# SAML21_Xplained_Pro_triple_input_power_s.net
KiCad netlist of a schematic drawn in Altium Designer
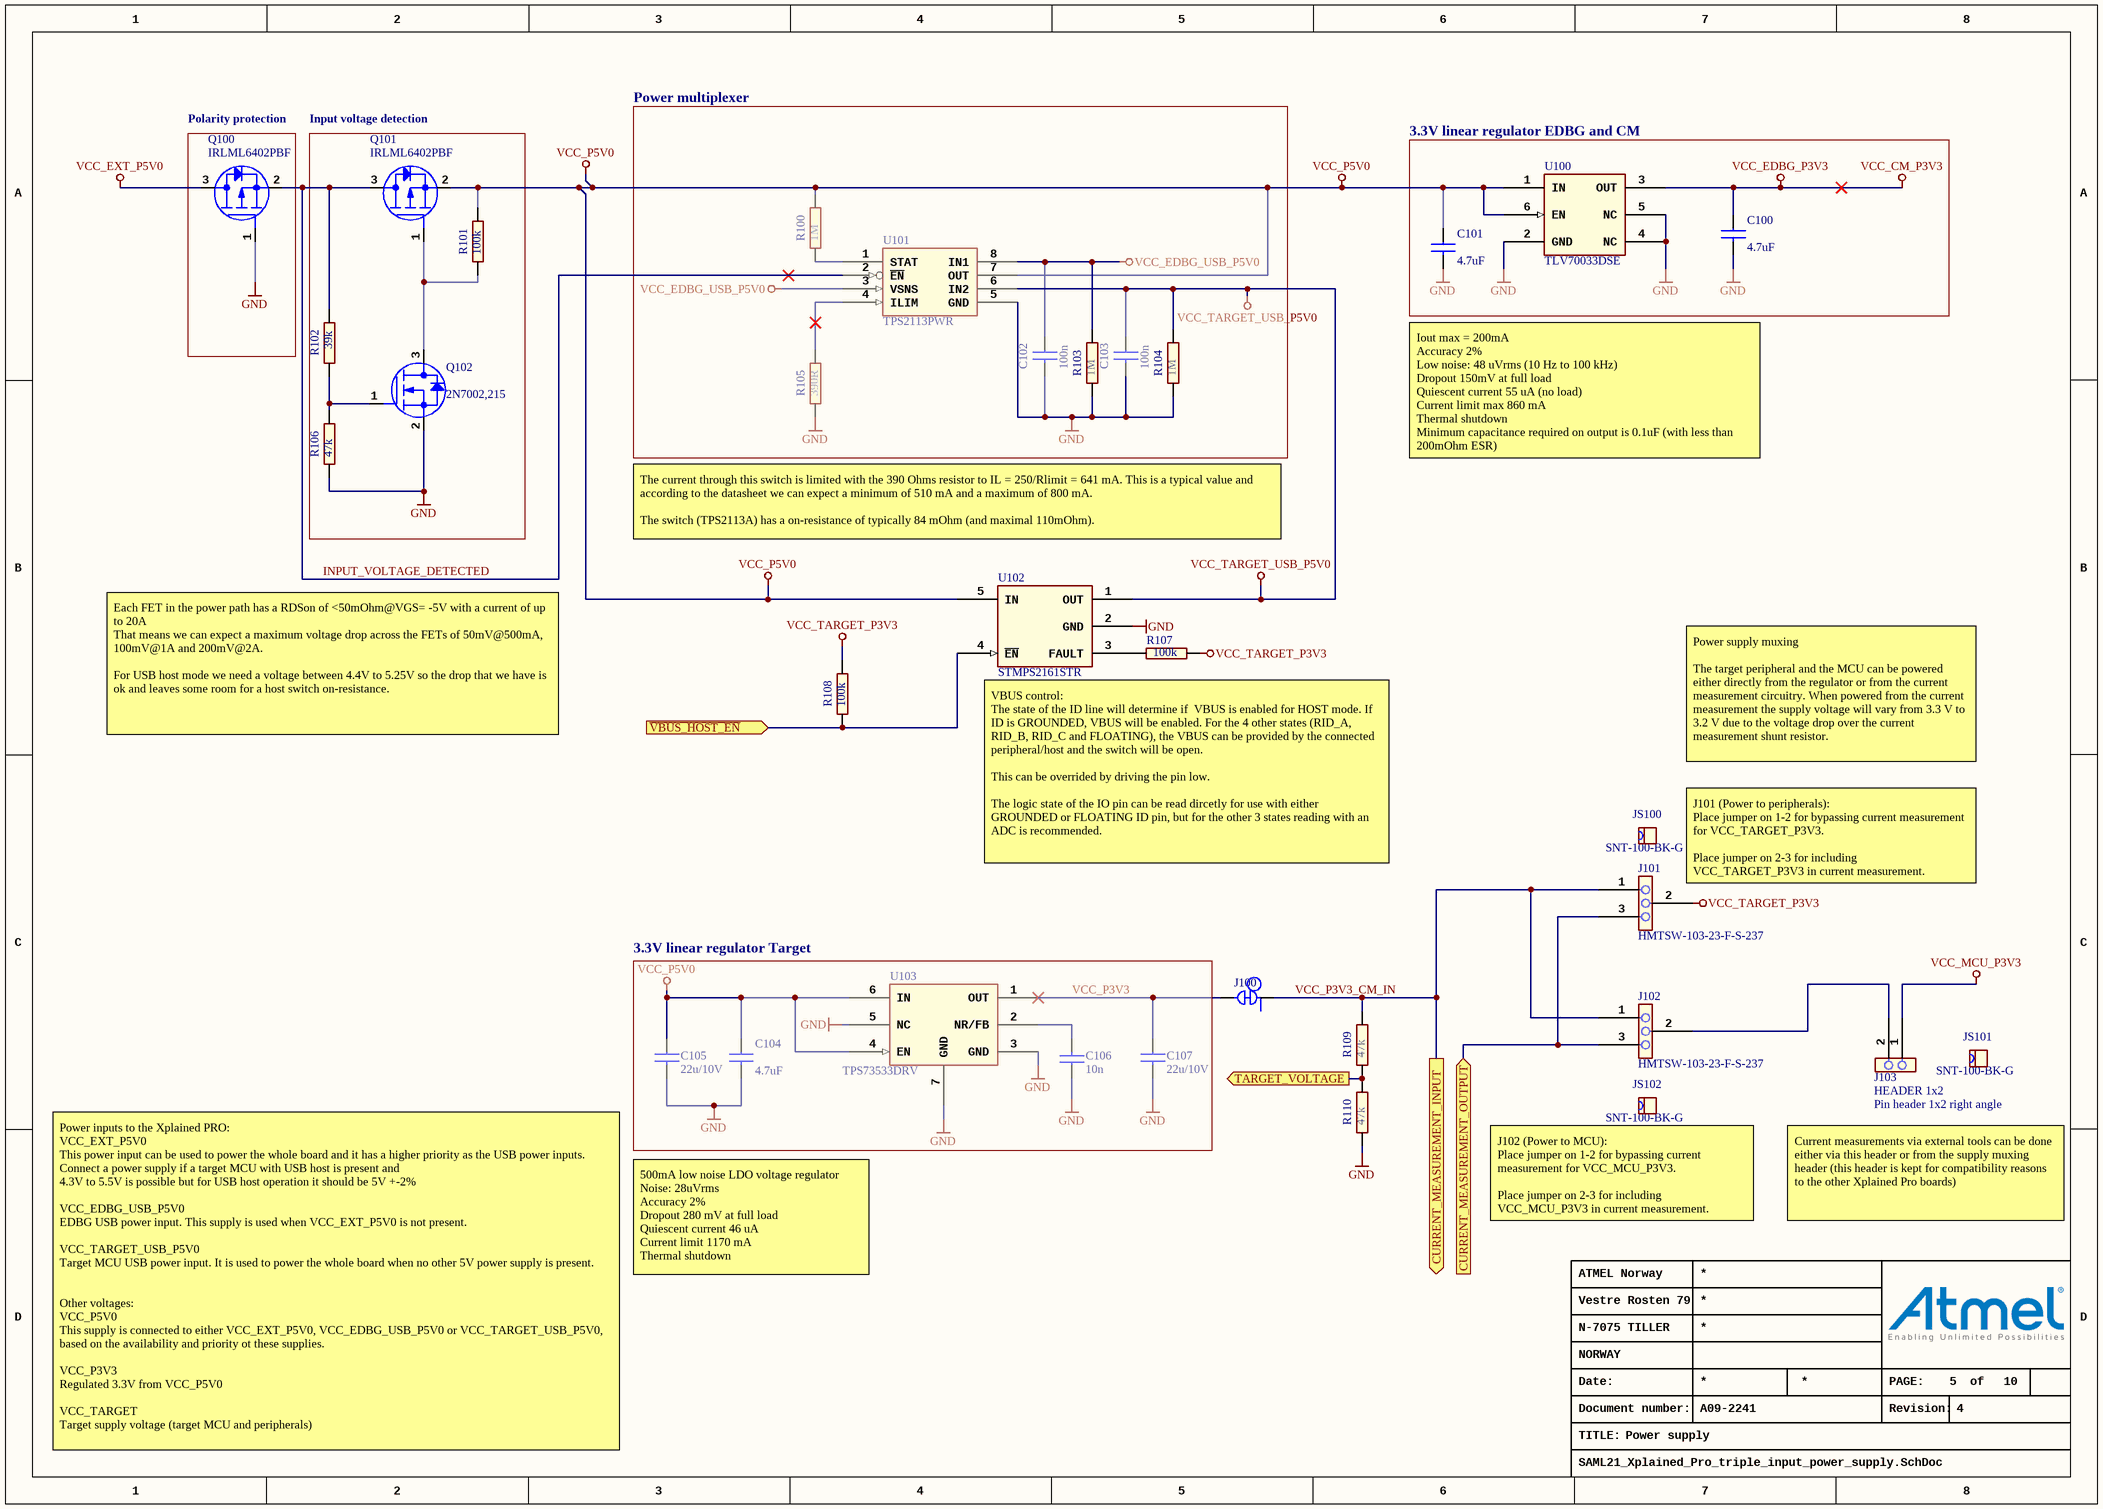
[diagram p0: SAML21_Xplained_Pro_triple_input_power_supply.SchDoc]

(export (version "E")
  (design (tool "Eeschema 10.0.6"))
  (components
    (comp (ref "C100")
      (value "4.7uF")
      (footprint "AP1-00117")
      (description "Ceramic capacitor, SMD 0603, X5R, 10V, 10% (de31036)")
      (fields (field (name "TOLERANCE") "10%") (field (name "MANUFACTURER") "tdk"))
      (libsource (lib "AltiumDbLib") (part "CAP-NONPOL"))
    )
    (comp (ref "C101")
      (value "4.7uF")
      (footprint "AP1-00117")
      (description "Ceramic capacitor, SMD 0603, X5R, 10V, 10% (de31036)")
      (fields (field (name "TOLERANCE") "10%") (field (name "MANUFACTURER") "tdk"))
      (libsource (lib "AltiumDbLib") (part "CAP-NONPOL"))
    )
    (comp (ref "C102")
      (value "100n")
      (footprint "AP1-00053")
      (description "Ceramic capacitor, SMD 0402, X7R, 16V, +/-10%")
      (fields (field (name "TOLERANCE") "16V, +/-10%") (field (name "MANUFACTURER") "Kemet"))
      (libsource (lib "AltiumDbLib") (part "CAP-NONPOL"))
    )
    (comp (ref "C103")
      (value "100n")
      (footprint "AP1-00053")
      (description "Ceramic capacitor, SMD 0402, X7R, 16V, +/-10%")
      (fields (field (name "TOLERANCE") "16V, +/-10%") (field (name "MANUFACTURER") "Kemet"))
      (libsource (lib "AltiumDbLib") (part "CAP-NONPOL"))
    )
    (comp (ref "C104")
      (value "4.7uF")
      (footprint "AP1-00117")
      (description "Ceramic capacitor, SMD 0603, X5R, 10V, 10% (de31036)")
      (fields (field (name "TOLERANCE") "10%") (field (name "MANUFACTURER") "tdk"))
      (libsource (lib "AltiumDbLib") (part "CAP-NONPOL"))
    )
    (comp (ref "C105")
      (value "22u/10V")
      (footprint "AP1-00003")
      (description "Ceramic capacitor, SMD 0805, X5R, 10V, Â±20%")
      (fields (field (name "MANUFACTURER") "tdk") (field (name "MPN") "C2012X5R1A226M/0.85"))
      (libsource (lib "AltiumDbLib") (part "CAP-NONPOL"))
    )
    (comp (ref "C106")
      (value "10n")
      (footprint "AP1-00053")
      (description "Ceramic capacitor, SMD 0402, X7R, 25V, +/-10%")
      (fields (field (name "TOLERANCE") "25V, +/-10%") (field (name "Comment") "CAP-NONPOL"))
      (libsource (lib "AltiumDbLib") (part "CAP-NONPOL"))
    )
    (comp (ref "C107")
      (value "22u/10V")
      (footprint "AP1-00003")
      (description "Ceramic capacitor, SMD 0805, X5R, 10V, Â±20%")
      (fields (field (name "MANUFACTURER") "tdk") (field (name "MPN") "C2012X5R1A226M/0.85"))
      (libsource (lib "AltiumDbLib") (part "CAP-NONPOL"))
    )
    (comp (ref "J100")
      (value "SMD-STRAP_CLOSED")
      (footprint "AP9-00044")
      (description "Default closed SMD strap, 0603 size")
      (libsource (lib "AltiumDbLib") (part "SMD-STRAP_CLOSED"))
    )
    (comp (ref "J101")
      (value "HMTSW-103-23-F-S-237")
      (footprint "AP8-00745")
      (description "1x3 pin header, 2.54mm pitch, Pin-in-Paste THM, 1mm hole")
      (fields
        (field (name "MANUFACTURER") "SAMTEC")
        (field (name "Comment") "Same as A08-1614 but with 1mm hole for optimal reflow soldering (no misalignment of the component)")
      )
      (libsource (lib "AltiumDbLib") (part "HEADER 1x3"))
    )
    (comp (ref "J102")
      (value "HMTSW-103-23-F-S-237")
      (footprint "AP8-00745")
      (description "1x3 pin header, 2.54mm pitch, Pin-in-Paste THM, 1mm hole")
      (fields
        (field (name "MANUFACTURER") "SAMTEC")
        (field (name "Comment") "Same as A08-1614 but with 1mm hole for optimal reflow soldering (no misalignment of the component)")
      )
      (libsource (lib "AltiumDbLib") (part "HEADER 1x3"))
    )
    (comp (ref "J103")
      (value "HEADER 1x2")
      (footprint "AP8-00367")
      (description "1x2 pin header, right angle, 2.54 mm pitch, through-hole")
      (fields
        (field (name "ALTIUM_VALUE") "Pin header 1x2 right angle")
        (field (name "MANUFACTURER") "Pro-data International Corp")
        (field (name "MPN") "2213R-2G")
      )
      (libsource (lib "AltiumDbLib") (part "HEADER 1x2"))
    )
    (comp (ref "JS100")
      (value "SNT-100-BK-G")
      (footprint "AP8-00525")
      (description "Jumper cap for 2.54mm pinheader")
      (fields (field (name "MANUFACTURER") "SAMTEC"))
      (libsource (lib "AltiumDbLib") (part "JUMPER_CAP"))
    )
    (comp (ref "JS101")
      (value "SNT-100-BK-G")
      (footprint "AP8-00525")
      (description "Jumper cap for 2.54mm pinheader")
      (fields (field (name "MANUFACTURER") "SAMTEC"))
      (libsource (lib "AltiumDbLib") (part "JUMPER_CAP"))
    )
    (comp (ref "JS102")
      (value "SNT-100-BK-G")
      (footprint "AP8-00525")
      (description "Jumper cap for 2.54mm pinheader")
      (fields (field (name "MANUFACTURER") "SAMTEC"))
      (libsource (lib "AltiumDbLib") (part "JUMPER_CAP"))
    )
    (comp (ref "Q100")
      (value "IRLML6402PBF")
      (footprint "AP5-00002")
      (description "P-ch. MOSFET. -30V, -3.7A continuous,RDS(ON)=0.05Ohm@VGS=-4,5V, RDS(ON)=0.08Ohm@VGS=-2.5V")
      (fields (field (name "MANUFACTURER") "International Rectifier") (field (name "Comment") "MOSFET_P_GSD"))
      (libsource (lib "AltiumDbLib") (part "MOSFET_P_GSD"))
    )
    (comp (ref "Q101")
      (value "IRLML6402PBF")
      (footprint "AP5-00002")
      (description "P-ch. MOSFET. -30V, -3.7A continuous,RDS(ON)=0.05Ohm@VGS=-4,5V, RDS(ON)=0.08Ohm@VGS=-2.5V")
      (fields (field (name "MANUFACTURER") "International Rectifier") (field (name "Comment") "MOSFET_P_GSD"))
      (libsource (lib "AltiumDbLib") (part "MOSFET_P_GSD"))
    )
    (comp (ref "Q102")
      (value "2N7002,215")
      (footprint "AP5-00002")
      (description "N-Channel MOSFET. 60V, 0.300A continuous, 1.2A Peak. RDS(ON) = 3.8Ohm@VGS=4.5V, VGS(th)<2.5V")
      (fields (field (name "MANUFACTURER") "NXP") (field (name "Comment") "MOSFET_N_GSD"))
      (libsource (lib "AltiumDbLib") (part "MOSFET_N_GSD"))
    )
    (comp (ref "R100")
      (value "1M")
      (footprint "AP2-00011")
      (description "Thick film resistor, SMD 0402, 1/16W, 1%")
      (fields (field (name "TOLERANCE") "1 %") (field (name "Comment") "R2"))
      (libsource (lib "AltiumDbLib") (part "R2"))
    )
    (comp (ref "R101")
      (value "100k")
      (footprint "AP2-00011")
      (description "Thick film resistor, SMD 0402, 1/16W, 1%")
      (fields (field (name "TOLERANCE") "1 %") (field (name "Comment") "R2"))
      (libsource (lib "AltiumDbLib") (part "R2"))
    )
    (comp (ref "R102")
      (value "39k")
      (footprint "AP2-00011")
      (description "Thick film resistor, SMD 0402, 1/16W, 1%")
      (fields (field (name "TOLERANCE") "1 %") (field (name "Comment") "R2"))
      (libsource (lib "AltiumDbLib") (part "R2"))
    )
    (comp (ref "R103")
      (value "1M")
      (footprint "AP2-00011")
      (description "Thick film resistor, SMD 0402, 1/16W, 1%")
      (fields (field (name "TOLERANCE") "1 %") (field (name "Comment") "R2"))
      (libsource (lib "AltiumDbLib") (part "R2"))
    )
    (comp (ref "R104")
      (value "1M")
      (footprint "AP2-00011")
      (description "Thick film resistor, SMD 0402, 1/16W, 1%")
      (fields (field (name "TOLERANCE") "1 %") (field (name "Comment") "R2"))
      (libsource (lib "AltiumDbLib") (part "R2"))
    )
    (comp (ref "R105")
      (value "390R")
      (footprint "AP2-00011")
      (description "Thick film resistor, SMD 0402, 1/16W, 1%")
      (fields (field (name "TOLERANCE") "1 %") (field (name "Comment") "R2"))
      (libsource (lib "AltiumDbLib") (part "R2"))
    )
    (comp (ref "R106")
      (value "47k")
      (footprint "AP2-00011")
      (description "Thick film resistor, SMD 0402, 1/16W, 1%")
      (fields (field (name "TOLERANCE") "1 %") (field (name "Comment") "R2"))
      (libsource (lib "AltiumDbLib") (part "R2"))
    )
    (comp (ref "R107")
      (value "100k")
      (footprint "AP2-00011")
      (description "Thick film resistor, SMD 0402, 1/16W, 1%")
      (fields (field (name "TOLERANCE") "1 %") (field (name "Comment") "R2"))
      (libsource (lib "") (part "R2_2"))
    )
    (comp (ref "R108")
      (value "100k")
      (footprint "AP2-00011")
      (description "Thick film resistor, SMD 0402, 1/16W, 1%")
      (fields (field (name "TOLERANCE") "1 %") (field (name "Comment") "R2"))
      (libsource (lib "AltiumDbLib") (part "R2"))
    )
    (comp (ref "R109")
      (value "47k")
      (footprint "AP2-00011")
      (description "Thick film resistor, SMD 0402, 1/16W, 1%")
      (fields (field (name "TOLERANCE") "1 %") (field (name "Comment") "R2"))
      (libsource (lib "") (part "R2_1"))
    )
    (comp (ref "R110")
      (value "47k")
      (footprint "AP2-00011")
      (description "Thick film resistor, SMD 0402, 1/16W, 1%")
      (fields (field (name "TOLERANCE") "1 %") (field (name "Comment") "R2"))
      (libsource (lib "") (part "R2_1"))
    )
    (comp (ref "U100")
      (value "TLV70033DSE")
      (footprint "AP6-00262")
      (description "LDO, 200 mA, Iq=31 uA, Vdo=250mV, Vout=3.3V, VIN= 2 V to 5.5V, SON-6 package")
      (fields (field (name "MANUFACTURER") "Texas Instruments") (field (name "Comment") "TLV70033"))
      (libsource (lib "AltiumDbLib") (part "TLV70033"))
    )
    (comp (ref "U101")
      (value "TPS2113PWR")
      (footprint "AP6-00054")
      (description "Autoswitching 2:1 Power Mux")
      (fields (field (name "MANUFACTURER") "Texas Instruments") (field (name "Comment") "TPS2112"))
      (libsource (lib "AltiumDbLib") (part "TPS2112"))
    )
    (comp (ref "U102")
      (value "STMPS2161STR")
      (footprint "AP6-00087")
      (description "Single channel power switch, 1A, reverse block, active low enabled.")
      (fields (field (name "TOLERANCE") "2.7 to 5.5V") (field (name "Comment") "STMPS2161"))
      (libsource (lib "AltiumDbLib") (part "STMPS2161"))
    )
    (comp (ref "U103")
      (value "TPS73533DRV")
      (footprint "AP6-00162")
      (fields (field (name "MANUFACTURER") "Texas Instruments") (field (name "Comment") "TPS735xxDRV"))
      (libsource (lib "AltiumDbLib") (part "TPS735xxDRV"))
    )
  )
  (nets
    (net (code "1") (name "/CURRENT_MEASUREMENT_OUTPUT") (class "Default")
      (node (ref "J101") (pin "3") (pinfunction "3_3") (pintype "passive"))
      (node (ref "J102") (pin "3") (pinfunction "3_3") (pintype "passive"))
    )
    (net (code "2") (name "/INPUT_VOLTAGE_DETECTED") (class "Default")
      (node (ref "Q100") (pin "2") (pinfunction "S_2") (pintype "passive"))
      (node (ref "Q101") (pin "3") (pinfunction "D_3") (pintype "passive"))
      (node (ref "R102") (pin "2") (pinfunction "2_2") (pintype "passive"))
      (node (ref "U101") (pin "2") (pinfunction "~{EN}_2") (pintype "input"))
    )
    (net (code "3") (name "/TARGET_VOLTAGE") (class "Default")
      (node (ref "R109") (pin "1") (pinfunction "1_1") (pintype "passive"))
      (node (ref "R110") (pin "2") (pinfunction "2_2") (pintype "passive"))
    )
    (net (code "4") (name "/VCC_P3V3") (class "Default")
      (node (ref "C107") (pin "1") (pinfunction "1_1") (pintype "passive"))
      (node (ref "J100") (pin "2") (pinfunction "2_2") (pintype "passive"))
      (node (ref "U103") (pin "1") (pinfunction "OUT_1") (pintype "power_in"))
    )
    (net (code "5") (name "/VCC_P3V3_CM_IN") (class "Default")
      (node (ref "J100") (pin "1") (pinfunction "1_1") (pintype "passive"))
      (node (ref "J101") (pin "1") (pinfunction "1_1") (pintype "passive"))
      (node (ref "J102") (pin "1") (pinfunction "1_1") (pintype "passive"))
      (node (ref "R109") (pin "2") (pinfunction "2_2") (pintype "passive"))
    )
    (net (code "6") (name "/~{VBUS_HOST_EN}") (class "Default")
      (node (ref "R108") (pin "1") (pinfunction "1_1") (pintype "passive"))
      (node (ref "U102") (pin "4") (pinfunction "~{EN}_4") (pintype "input"))
    )
    (net (code "7") (name "GND") (class "Default")
      (node (ref "C100") (pin "2") (pinfunction "2_2") (pintype "passive"))
      (node (ref "C101") (pin "2") (pinfunction "2_2") (pintype "passive"))
      (node (ref "C102") (pin "2") (pinfunction "2_2") (pintype "passive"))
      (node (ref "C103") (pin "2") (pinfunction "2_2") (pintype "passive"))
      (node (ref "C104") (pin "2") (pinfunction "2_2") (pintype "passive"))
      (node (ref "C105") (pin "2") (pinfunction "2_2") (pintype "passive"))
      (node (ref "C106") (pin "1") (pinfunction "1_1") (pintype "passive"))
      (node (ref "C107") (pin "2") (pinfunction "2_2") (pintype "passive"))
      (node (ref "Q100") (pin "1") (pinfunction "G_1") (pintype "passive"))
      (node (ref "Q102") (pin "2") (pinfunction "S_2") (pintype "passive"))
      (node (ref "R103") (pin "1") (pinfunction "1_1") (pintype "passive"))
      (node (ref "R104") (pin "1") (pinfunction "1_1") (pintype "passive"))
      (node (ref "R105") (pin "1") (pinfunction "1_1") (pintype "passive"))
      (node (ref "R106") (pin "1") (pinfunction "1_1") (pintype "passive"))
      (node (ref "R110") (pin "1") (pinfunction "1_1") (pintype "passive"))
      (node (ref "U100") (pin "2") (pinfunction "GND_2") (pintype "power_in"))
      (node (ref "U100") (pin "4") (pinfunction "NC_4") (pintype "passive"))
      (node (ref "U100") (pin "5") (pinfunction "NC_5") (pintype "passive"))
      (node (ref "U101") (pin "5") (pinfunction "GND_5") (pintype "power_in"))
      (node (ref "U102") (pin "2") (pinfunction "GND_2") (pintype "power_in"))
      (node (ref "U103") (pin "3") (pinfunction "GND_3") (pintype "power_in"))
      (node (ref "U103") (pin "5") (pinfunction "NC_5") (pintype "passive"))
      (node (ref "U103") (pin "7") (pinfunction "GND_7") (pintype "power_in"))
    )
    (net (code "8") (name "Net-(J102-Pad2)") (class "Default")
      (node (ref "J102") (pin "2") (pinfunction "2_2") (pintype "passive"))
      (node (ref "J103") (pin "2") (pinfunction "2_2") (pintype "passive"))
    )
    (net (code "9") (name "Net-(Q101-G)") (class "Default")
      (node (ref "Q101") (pin "1") (pinfunction "G_1") (pintype "passive"))
      (node (ref "Q102") (pin "3") (pinfunction "D_3") (pintype "passive"))
      (node (ref "R101") (pin "1") (pinfunction "1_1") (pintype "passive"))
    )
    (net (code "10") (name "Net-(Q102-G)") (class "Default")
      (node (ref "Q102") (pin "1") (pinfunction "G_1") (pintype "passive"))
      (node (ref "R102") (pin "1") (pinfunction "1_1") (pintype "passive"))
      (node (ref "R106") (pin "2") (pinfunction "2_2") (pintype "passive"))
    )
    (net (code "11") (name "Net-(U101-ILIM)") (class "Default")
      (node (ref "R105") (pin "2") (pinfunction "2_2") (pintype "passive"))
      (node (ref "U101") (pin "4") (pinfunction "ILIM_4") (pintype "input"))
    )
    (net (code "12") (name "Net-(U101-STAT)") (class "Default")
      (node (ref "R100") (pin "1") (pinfunction "1_1") (pintype "passive"))
      (node (ref "U101") (pin "1") (pinfunction "STAT_1") (pintype "open_collector"))
    )
    (net (code "13") (name "Net-(U102-FAULT)") (class "Default")
      (node (ref "R107") (pin "2") (pinfunction "2_2") (pintype "passive"))
      (node (ref "U102") (pin "3") (pinfunction "FAULT_3") (pintype "open_collector"))
    )
    (net (code "14") (name "Net-(U103-NR{slash}FB)") (class "Default")
      (node (ref "C106") (pin "2") (pinfunction "2_2") (pintype "passive"))
      (node (ref "U103") (pin "2") (pinfunction "NR/FB_2") (pintype "passive"))
    )
    (net (code "15") (name "VCC_CM_P3V3") (class "Default")
      (node (ref "C100") (pin "1") (pinfunction "1_1") (pintype "passive"))
      (node (ref "U100") (pin "3") (pinfunction "OUT_3") (pintype "power_in"))
    )
    (net (code "16") (name "VCC_EDBG_USB_P5V0") (class "Default")
      (node (ref "C102") (pin "1") (pinfunction "1_1") (pintype "passive"))
      (node (ref "R103") (pin "2") (pinfunction "2_2") (pintype "passive"))
      (node (ref "U101") (pin "3") (pinfunction "VSNS_3") (pintype "input"))
      (node (ref "U101") (pin "8") (pinfunction "IN1_8") (pintype "power_in"))
    )
    (net (code "17") (name "VCC_EXT_P5V0") (class "Default")
      (node (ref "Q100") (pin "3") (pinfunction "D_3") (pintype "passive"))
    )
    (net (code "18") (name "VCC_MCU_P3V3") (class "Default")
      (node (ref "J103") (pin "1") (pinfunction "1_1") (pintype "passive"))
    )
    (net (code "19") (name "VCC_P5V0") (class "Default")
      (node (ref "C101") (pin "1") (pinfunction "1_1") (pintype "passive"))
      (node (ref "C104") (pin "1") (pinfunction "1_1") (pintype "passive"))
      (node (ref "C105") (pin "1") (pinfunction "1_1") (pintype "passive"))
      (node (ref "Q101") (pin "2") (pinfunction "S_2") (pintype "passive"))
      (node (ref "R100") (pin "2") (pinfunction "2_2") (pintype "passive"))
      (node (ref "R101") (pin "2") (pinfunction "2_2") (pintype "passive"))
      (node (ref "U100") (pin "1") (pinfunction "IN_1") (pintype "power_in"))
      (node (ref "U100") (pin "6") (pinfunction "EN_6") (pintype "input"))
      (node (ref "U101") (pin "7") (pinfunction "OUT_7") (pintype "power_in"))
      (node (ref "U102") (pin "5") (pinfunction "IN_5") (pintype "power_in"))
      (node (ref "U103") (pin "4") (pinfunction "EN_4") (pintype "input"))
      (node (ref "U103") (pin "6") (pinfunction "IN_6") (pintype "power_in"))
    )
    (net (code "20") (name "VCC_TARGET_P3V3") (class "Default")
      (node (ref "J101") (pin "2") (pinfunction "2_2") (pintype "passive"))
      (node (ref "R107") (pin "1") (pinfunction "1_1") (pintype "passive"))
      (node (ref "R108") (pin "2") (pinfunction "2_2") (pintype "passive"))
    )
    (net (code "21") (name "VCC_TARGET_USB_P5V0") (class "Default")
      (node (ref "C103") (pin "1") (pinfunction "1_1") (pintype "passive"))
      (node (ref "R104") (pin "2") (pinfunction "2_2") (pintype "passive"))
      (node (ref "U101") (pin "6") (pinfunction "IN2_6") (pintype "power_in"))
      (node (ref "U102") (pin "1") (pinfunction "OUT_1") (pintype "power_in"))
    )
  )
)
